# smarties_sorter.net
KiCad netlist of a schematic drawn in EAGLE
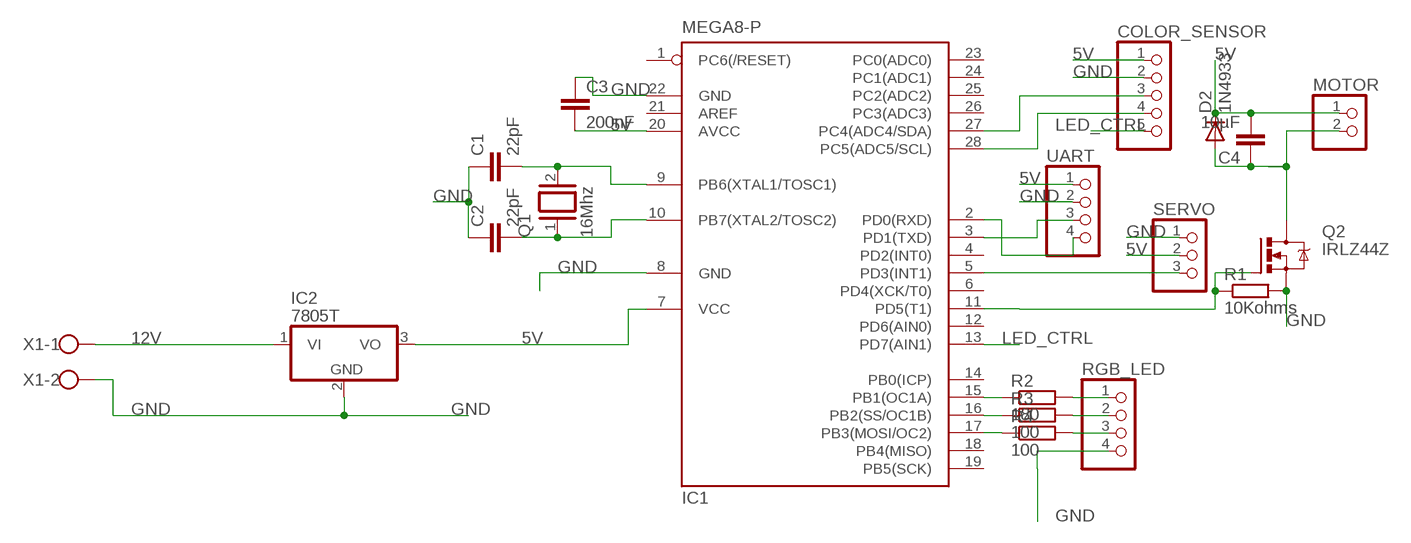
[diagram p0: schematic, sheet 1]

(export (version "E")
  (design (tool "Eeschema 10.0.6"))
  (components
    (comp (ref "C1")
      (value "22pF")
      (footprint "eagle-import:C5B5")
      (libsource (lib "eagle-import") (part "C5/5"))
    )
    (comp (ref "C2")
      (value "22pF")
      (footprint "eagle-import:C5B5")
      (libsource (lib "eagle-import") (part "C5/5"))
    )
    (comp (ref "C3")
      (value "200nF")
      (footprint "eagle-import:C5B3")
      (libsource (lib "eagle-import") (part "C5/3"))
    )
    (comp (ref "C4")
      (value "10µF")
      (footprint "eagle-import:C5B5")
      (libsource (lib "eagle-import") (part "C5/5"))
    )
    (comp (ref "COLOR_SENSOR")
      (value "PINHD-1X5")
      (footprint "eagle-import:1X05")
      (libsource (lib "eagle-import") (part "PINHD-1X5"))
    )
    (comp (ref "D2")
      (value "1N4933")
      (footprint "eagle-import:DO41-10")
      (libsource (lib "eagle-import") (part "1N4933"))
    )
    (comp (ref "IC1")
      (value "MEGA8-P")
      (footprint "eagle-import:DIL28-3")
      (libsource (lib "eagle-import") (part "MEGA8-P"))
    )
    (comp (ref "IC2")
      (value "7805T")
      (footprint "eagle-import:TO220H")
      (libsource (lib "eagle-import") (part "78T05"))
    )
    (comp (ref "MOTOR")
      (value "PINHD-1X2")
      (footprint "eagle-import:1X02")
      (libsource (lib "eagle-import") (part "PINHD-1X2"))
    )
    (comp (ref "Q1")
      (value "16Mhz")
      (footprint "eagle-import:QS")
      (libsource (lib "eagle-import") (part "XTAL/S"))
    )
    (comp (ref "Q2")
      (value "IRLZ44Z")
      (footprint "eagle-import:TO220BH")
      (libsource (lib "eagle-import") (part "IRLZ44Z"))
    )
    (comp (ref "R1")
      (value "10Kohms")
      (footprint "eagle-import:0414_15")
      (libsource (lib "eagle-import") (part "R-EU_0414/15"))
    )
    (comp (ref "R2")
      (value "180")
      (footprint "eagle-import:0411_12")
      (libsource (lib "eagle-import") (part "resistor_R-EU_0411/12"))
    )
    (comp (ref "R3")
      (value "100")
      (footprint "eagle-import:0411_12")
      (libsource (lib "eagle-import") (part "resistor_R-EU_0411/12"))
    )
    (comp (ref "R4")
      (value "100")
      (footprint "eagle-import:0411_12")
      (libsource (lib "eagle-import") (part "resistor_R-EU_0411/12"))
    )
    (comp (ref "RGB_LED")
      (value "PINHD-1X4")
      (footprint "eagle-import:1X04")
      (libsource (lib "eagle-import") (part "PINHD-1X4"))
    )
    (comp (ref "SERVO")
      (value "PINHD-1X3")
      (footprint "eagle-import:1X03")
      (libsource (lib "eagle-import") (part "PINHD-1X3"))
    )
    (comp (ref "UART")
      (value "PINHD-1X4")
      (footprint "eagle-import:1X04")
      (libsource (lib "eagle-import") (part "PINHD-1X4"))
    )
    (comp (ref "X1")
      (value "W237-102")
      (footprint "eagle-import:W237-102")
      (fields (field (name "MPN") "237-102"))
      (libsource (lib "eagle-import") (part "W237-102"))
    )
  )
  (nets
    (net (code "1") (name "/5V") (class "Default")
      (node (ref "C3") (pin "2") (pinfunction "2_2") (pintype "passive"))
      (node (ref "C4") (pin "2") (pinfunction "2_2") (pintype "passive"))
      (node (ref "COLOR_SENSOR") (pin "1") (pinfunction "1_1") (pintype "passive"))
      (node (ref "D2") (pin "C") (pinfunction "C_C") (pintype "passive"))
      (node (ref "IC1") (pin "20") (pinfunction "AVCC_20") (pintype "power_in"))
      (node (ref "IC1") (pin "7") (pinfunction "VCC_7") (pintype "power_in"))
      (node (ref "IC2") (pin "3") (pinfunction "VO_3") (pintype "passive"))
      (node (ref "MOTOR") (pin "1") (pinfunction "1_1") (pintype "passive"))
      (node (ref "SERVO") (pin "2") (pinfunction "2_2") (pintype "passive"))
      (node (ref "UART") (pin "1") (pinfunction "1_1") (pintype "passive"))
    )
    (net (code "2") (name "/12V") (class "Default")
      (node (ref "IC2") (pin "1") (pinfunction "VI_1") (pintype "input"))
      (node (ref "X1") (pin "1") (pinfunction "KL_1") (pintype "passive"))
    )
    (net (code "3") (name "/GND") (class "Default")
      (node (ref "C1") (pin "1") (pinfunction "1_1") (pintype "passive"))
      (node (ref "C2") (pin "1") (pinfunction "1_1") (pintype "passive"))
      (node (ref "C3") (pin "1") (pinfunction "1_1") (pintype "passive"))
      (node (ref "COLOR_SENSOR") (pin "2") (pinfunction "2_2") (pintype "passive"))
      (node (ref "IC1") (pin "22") (pinfunction "GND_22") (pintype "power_in"))
      (node (ref "IC1") (pin "8") (pinfunction "GND_8") (pintype "power_in"))
      (node (ref "IC2") (pin "2") (pinfunction "GND_2") (pintype "passive"))
      (node (ref "Q2") (pin "S") (pinfunction "S_S") (pintype "passive"))
      (node (ref "R1") (pin "2") (pinfunction "2_2") (pintype "passive"))
      (node (ref "RGB_LED") (pin "4") (pinfunction "4_4") (pintype "passive"))
      (node (ref "SERVO") (pin "1") (pinfunction "1_1") (pintype "passive"))
      (node (ref "UART") (pin "2") (pinfunction "2_2") (pintype "passive"))
      (node (ref "X1") (pin "2") (pinfunction "KL_2") (pintype "passive"))
    )
    (net (code "4") (name "/LED_CTRL") (class "Default")
      (node (ref "COLOR_SENSOR") (pin "5") (pinfunction "5_5") (pintype "passive"))
      (node (ref "IC1") (pin "13") (pinfunction "PD7(AIN1)_13") (pintype "bidirectional"))
    )
    (net (code "5") (name "Net-(C4-Pad1)") (class "Default")
      (node (ref "C4") (pin "1") (pinfunction "1_1") (pintype "passive"))
      (node (ref "D2") (pin "A") (pinfunction "A_A") (pintype "passive"))
      (node (ref "MOTOR") (pin "2") (pinfunction "2_2") (pintype "passive"))
      (node (ref "Q2") (pin "D") (pinfunction "D_D") (pintype "passive"))
    )
    (net (code "6") (name "Net-(IC1-PB1(OC1A))") (class "Default")
      (node (ref "IC1") (pin "15") (pinfunction "PB1(OC1A)_15") (pintype "bidirectional"))
      (node (ref "R2") (pin "1") (pinfunction "1_1") (pintype "passive"))
    )
    (net (code "7") (name "Net-(IC1-PB2(SS{slash}OC1B))") (class "Default")
      (node (ref "IC1") (pin "16") (pinfunction "PB2(SS/OC1B)_16") (pintype "bidirectional"))
      (node (ref "R3") (pin "1") (pinfunction "1_1") (pintype "passive"))
    )
    (net (code "8") (name "Net-(IC1-PB3(MOSI{slash}OC2))") (class "Default")
      (node (ref "IC1") (pin "17") (pinfunction "PB3(MOSI/OC2)_17") (pintype "bidirectional"))
      (node (ref "R4") (pin "1") (pinfunction "1_1") (pintype "passive"))
    )
    (net (code "9") (name "Net-(IC1-PB6(XTAL1{slash}TOSC1))") (class "Default")
      (node (ref "C1") (pin "2") (pinfunction "2_2") (pintype "passive"))
      (node (ref "IC1") (pin "9") (pinfunction "PB6(XTAL1/TOSC1)_9") (pintype "bidirectional"))
      (node (ref "Q1") (pin "2") (pinfunction "2_2") (pintype "passive"))
    )
    (net (code "10") (name "Net-(IC1-PB7(XTAL2{slash}TOSC2))") (class "Default")
      (node (ref "C2") (pin "2") (pinfunction "2_2") (pintype "passive"))
      (node (ref "IC1") (pin "10") (pinfunction "PB7(XTAL2/TOSC2)_10") (pintype "bidirectional"))
      (node (ref "Q1") (pin "1") (pinfunction "1_1") (pintype "passive"))
    )
    (net (code "11") (name "Net-(IC1-PC4(ADC4{slash}SDA))") (class "Default")
      (node (ref "COLOR_SENSOR") (pin "3") (pinfunction "3_3") (pintype "passive"))
      (node (ref "IC1") (pin "27") (pinfunction "PC4(ADC4/SDA)_27") (pintype "bidirectional"))
    )
    (net (code "12") (name "Net-(IC1-PC5(ADC5{slash}SCL))") (class "Default")
      (node (ref "COLOR_SENSOR") (pin "4") (pinfunction "4_4") (pintype "passive"))
      (node (ref "IC1") (pin "28") (pinfunction "PC5(ADC5/SCL)_28") (pintype "bidirectional"))
    )
    (net (code "13") (name "Net-(IC1-PD0(RXD))") (class "Default")
      (node (ref "IC1") (pin "2") (pinfunction "PD0(RXD)_2") (pintype "bidirectional"))
      (node (ref "UART") (pin "4") (pinfunction "4_4") (pintype "passive"))
    )
    (net (code "14") (name "Net-(IC1-PD1(TXD))") (class "Default")
      (node (ref "IC1") (pin "3") (pinfunction "PD1(TXD)_3") (pintype "bidirectional"))
      (node (ref "UART") (pin "3") (pinfunction "3_3") (pintype "passive"))
    )
    (net (code "15") (name "Net-(IC1-PD3(INT1))") (class "Default")
      (node (ref "IC1") (pin "5") (pinfunction "PD3(INT1)_5") (pintype "bidirectional"))
      (node (ref "SERVO") (pin "3") (pinfunction "3_3") (pintype "passive"))
    )
    (net (code "16") (name "Net-(IC1-PD5(T1))") (class "Default")
      (node (ref "IC1") (pin "11") (pinfunction "PD5(T1)_11") (pintype "bidirectional"))
      (node (ref "Q2") (pin "G") (pinfunction "G_G") (pintype "passive"))
      (node (ref "R1") (pin "1") (pinfunction "1_1") (pintype "passive"))
    )
    (net (code "17") (name "Net-(R2-Pad2)") (class "Default")
      (node (ref "R2") (pin "2") (pinfunction "2_2") (pintype "passive"))
      (node (ref "RGB_LED") (pin "1") (pinfunction "1_1") (pintype "passive"))
    )
    (net (code "18") (name "Net-(R3-Pad2)") (class "Default")
      (node (ref "R3") (pin "2") (pinfunction "2_2") (pintype "passive"))
      (node (ref "RGB_LED") (pin "2") (pinfunction "2_2") (pintype "passive"))
    )
    (net (code "19") (name "Net-(R4-Pad2)") (class "Default")
      (node (ref "R4") (pin "2") (pinfunction "2_2") (pintype "passive"))
      (node (ref "RGB_LED") (pin "3") (pinfunction "3_3") (pintype "passive"))
    )
    (net (code "20") (name "unconnected-(IC1-AREF-Pad21)") (class "Default")
      (node (ref "IC1") (pin "21") (pinfunction "AREF_21") (pintype "passive"))
    )
    (net (code "21") (name "unconnected-(IC1-PB0(ICP)-Pad14)") (class "Default")
      (node (ref "IC1") (pin "14") (pinfunction "PB0(ICP)_14") (pintype "bidirectional"))
    )
    (net (code "22") (name "unconnected-(IC1-PB4(MISO)-Pad18)") (class "Default")
      (node (ref "IC1") (pin "18") (pinfunction "PB4(MISO)_18") (pintype "bidirectional"))
    )
    (net (code "23") (name "unconnected-(IC1-PB5(SCK)-Pad19)") (class "Default")
      (node (ref "IC1") (pin "19") (pinfunction "PB5(SCK)_19") (pintype "bidirectional"))
    )
    (net (code "24") (name "unconnected-(IC1-PC0(ADC0)-Pad23)") (class "Default")
      (node (ref "IC1") (pin "23") (pinfunction "PC0(ADC0)_23") (pintype "bidirectional"))
    )
    (net (code "25") (name "unconnected-(IC1-PC1(ADC1)-Pad24)") (class "Default")
      (node (ref "IC1") (pin "24") (pinfunction "PC1(ADC1)_24") (pintype "bidirectional"))
    )
    (net (code "26") (name "unconnected-(IC1-PC2(ADC2)-Pad25)") (class "Default")
      (node (ref "IC1") (pin "25") (pinfunction "PC2(ADC2)_25") (pintype "bidirectional"))
    )
    (net (code "27") (name "unconnected-(IC1-PC3(ADC3)-Pad26)") (class "Default")
      (node (ref "IC1") (pin "26") (pinfunction "PC3(ADC3)_26") (pintype "bidirectional"))
    )
    (net (code "28") (name "unconnected-(IC1-PC6({slash}RESET)-Pad1)") (class "Default")
      (node (ref "IC1") (pin "1") (pinfunction "PC6(/RESET)_1") (pintype "bidirectional"))
    )
    (net (code "29") (name "unconnected-(IC1-PD2(INT0)-Pad4)") (class "Default")
      (node (ref "IC1") (pin "4") (pinfunction "PD2(INT0)_4") (pintype "bidirectional"))
    )
    (net (code "30") (name "unconnected-(IC1-PD4(XCK{slash}T0)-Pad6)") (class "Default")
      (node (ref "IC1") (pin "6") (pinfunction "PD4(XCK/T0)_6") (pintype "bidirectional"))
    )
    (net (code "31") (name "unconnected-(IC1-PD6(AIN0)-Pad12)") (class "Default")
      (node (ref "IC1") (pin "12") (pinfunction "PD6(AIN0)_12") (pintype "bidirectional"))
    )
  )
)
